# 5V_LDO.net
KiCad netlist of a schematic drawn in Altium Designer
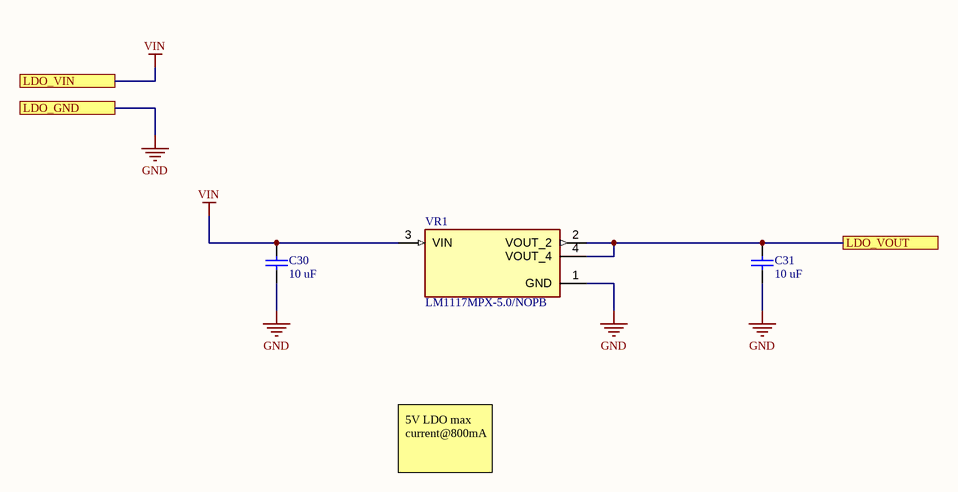
[diagram p0: 5V_LDO.SchDoc]

(export (version "E")
  (design (tool "Eeschema 10.0.6"))
  (components
    (comp (ref "C30")
      (value "10 uF")
      (footprint "CAPC2013X95X50LL10T25")
      (description "Chip Capacitor, 10 uF, +/- 10%, 6.3 V, -55 to 85 degC, 0805 (2012 Metric), RoHS, Tape and Reel")
      (fields (field (name "TOLERANCE") "±10%") (field (name "MANUFACTURER") "Taiyo Yuden"))
      (libsource (lib "Altium Content Vault") (part "CAP-NP-2"))
    )
    (comp (ref "C31")
      (value "10 uF")
      (footprint "CAPC2013X95X50LL10T25")
      (description "Chip Capacitor, 10 uF, +/- 10%, 6.3 V, -55 to 85 degC, 0805 (2012 Metric), RoHS, Tape and Reel")
      (fields (field (name "TOLERANCE") "±10%") (field (name "MANUFACTURER") "Taiyo Yuden"))
      (libsource (lib "Altium Content Vault") (part "CAP-NP-2"))
    )
    (comp (ref "VR1")
      (value "LM1117MPX-5.0/NOPB")
      (footprint "LM1117MPX-50NOPB:VREG_LM1117MPX-5.0/NOPB")
      (description "800-mA 15-V linear voltage regulator 4-SOT-223 0 to 125")
      (fields (field (name "MF") "{'manufacturer': u'ON Semiconductor'}"))
      (libsource (lib "LM1117MPX-50NOPB") (part "LM1117MPX-5.0/NOPB"))
    )
  )
  (nets
    (net (code "1") (name "/LDO_VOUT") (class "Default")
      (node (ref "C31") (pin "2") (pinfunction "2_2") (pintype "passive"))
      (node (ref "VR1") (pin "2") (pinfunction "VOUT_2_2") (pintype "output"))
      (node (ref "VR1") (pin "4") (pinfunction "VOUT_4_4") (pintype "passive"))
    )
    (net (code "2") (name "GND") (class "Default")
      (node (ref "C30") (pin "1") (pinfunction "1_1") (pintype "passive"))
      (node (ref "C31") (pin "1") (pinfunction "1_1") (pintype "passive"))
      (node (ref "VR1") (pin "1") (pinfunction "GND_1") (pintype "power_in"))
    )
    (net (code "3") (name "VIN") (class "Default")
      (node (ref "C30") (pin "2") (pinfunction "2_2") (pintype "passive"))
      (node (ref "VR1") (pin "3") (pinfunction "VIN_3") (pintype "input"))
    )
  )
)
